# Qwiic_EEPROM.net
KiCad netlist of a schematic drawn in EAGLE
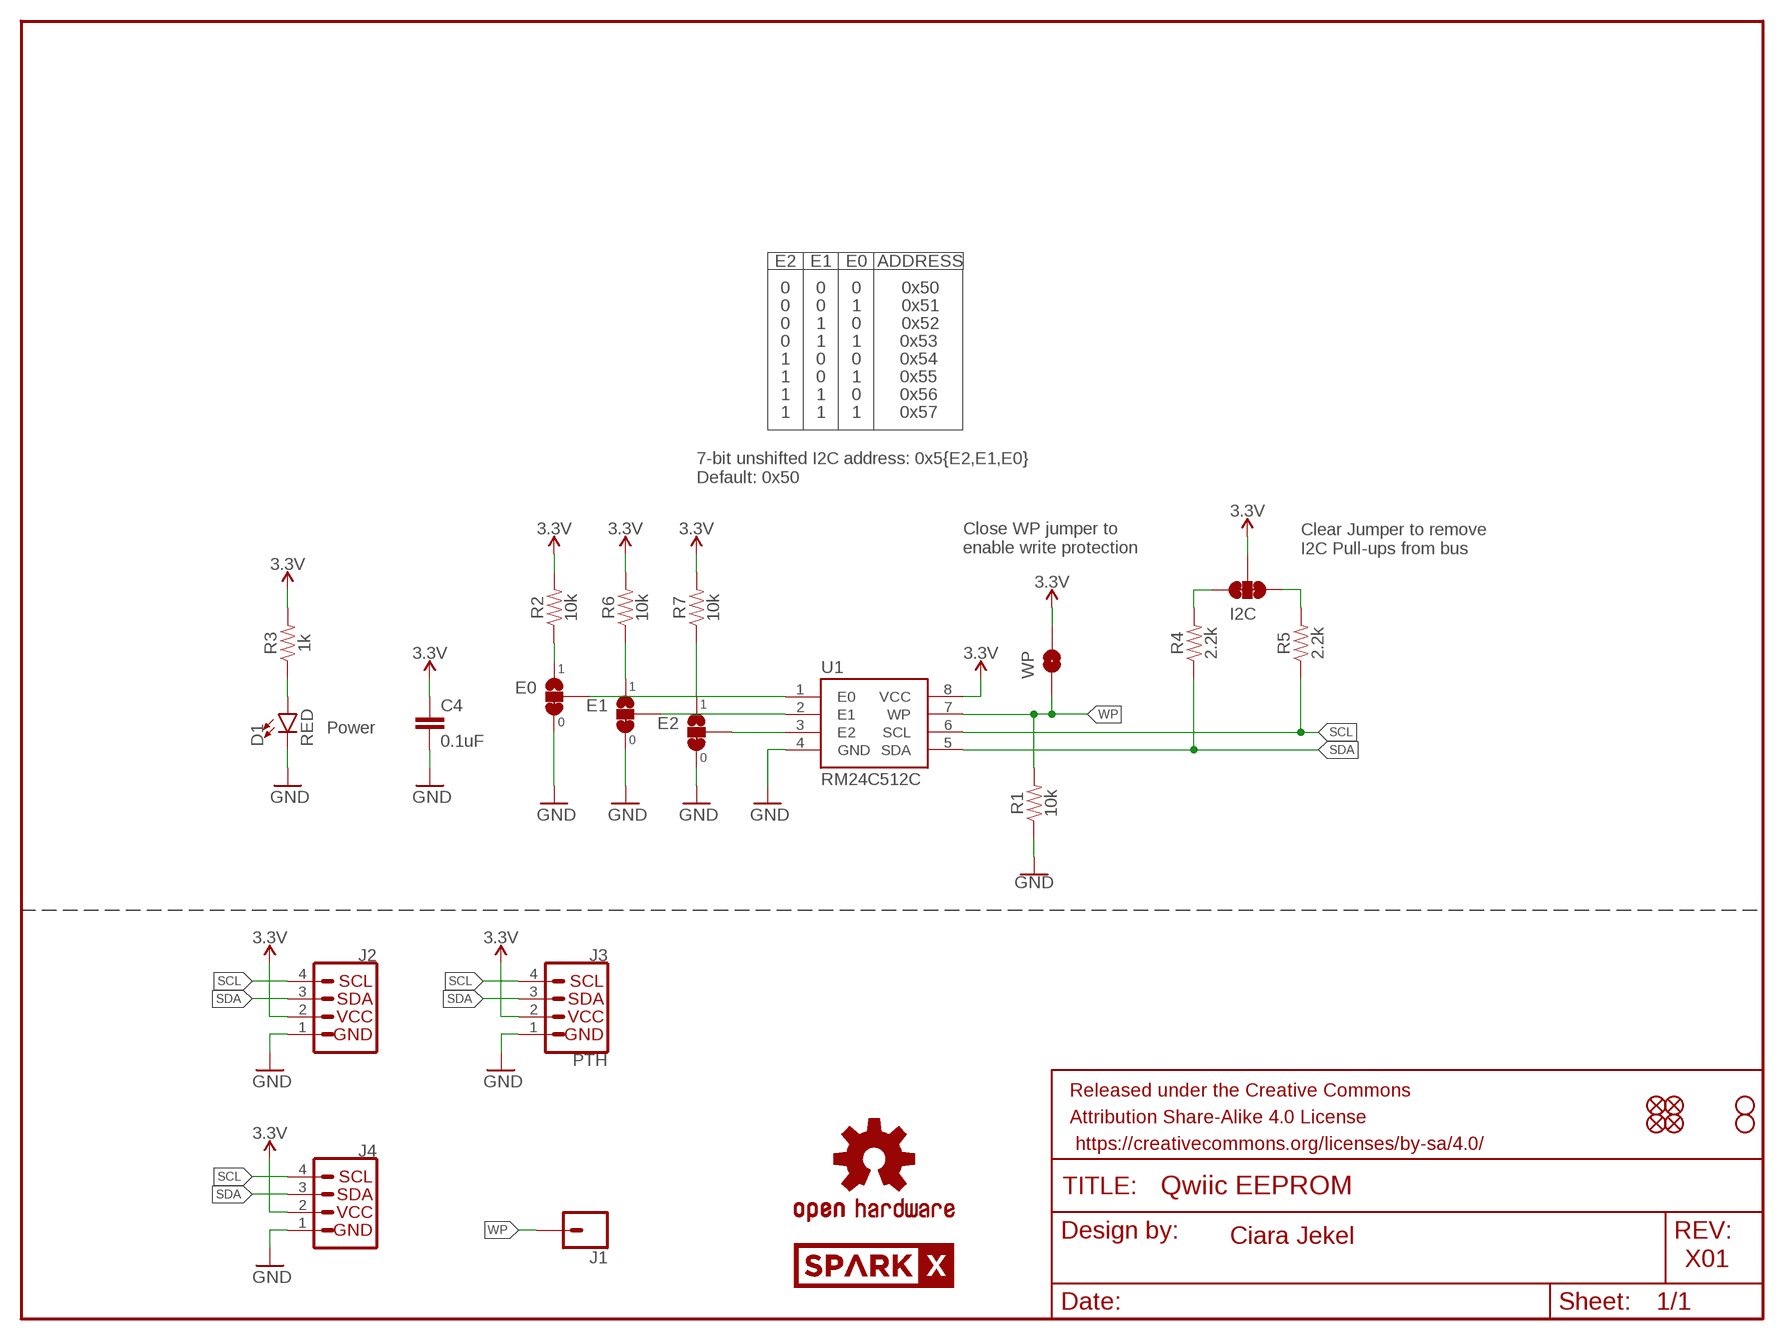
[diagram p0: schematic, sheet 1]

(export (version "E")
  (design (tool "Eeschema 10.0.6"))
  (components
    (comp (ref "C4")
      (value "0.1uF")
      (footprint "eagle-import:0603")
      (libsource (lib "eagle-import") (part "0.1UF-0603-25V-(+80/-20%)"))
    )
    (comp (ref "D1")
      (value "RED")
      (footprint "eagle-import:LED-0603")
      (libsource (lib "eagle-import") (part "LED-RED0603"))
    )
    (comp (ref "E0")
      (value "JUMPER-SMT_3_1-NC_TRACE_SILK")
      (footprint "eagle-import:SMT-JUMPER_3_1-NC_TRACE_SILK")
      (libsource (lib "eagle-import") (part "JUMPER-SMT_3_1-NC_TRACE_SILK"))
    )
    (comp (ref "E1")
      (value "JUMPER-SMT_3_1-NC_TRACE_SILK")
      (footprint "eagle-import:SMT-JUMPER_3_1-NC_TRACE_SILK")
      (libsource (lib "eagle-import") (part "JUMPER-SMT_3_1-NC_TRACE_SILK"))
    )
    (comp (ref "E2")
      (value "JUMPER-SMT_3_1-NC_TRACE_SILK")
      (footprint "eagle-import:SMT-JUMPER_3_1-NC_TRACE_SILK")
      (libsource (lib "eagle-import") (part "JUMPER-SMT_3_1-NC_TRACE_SILK"))
    )
    (comp (ref "FRAME1")
      (value "FRAME-LETTER")
      (footprint "eagle-import:CREATIVE_COMMONS")
      (libsource (lib "eagle-import") (part "FRAME-LETTER"))
    )
    (comp (ref "I2C")
      (value "JUMPER-SMT_3_2-NC_TRACE_SILK")
      (footprint "eagle-import:SMT-JUMPER_3_2-NC_TRACE_SILK")
      (libsource (lib "eagle-import") (part "JUMPER-SMT_3_2-NC_TRACE_SILK"))
    )
    (comp (ref "J1")
      (value "CONN_01PTH_NO_SILK_YES_STOP")
      (footprint "eagle-import:1X01_NO_SILK")
      (libsource (lib "eagle-import") (part "CONN_01PTH_NO_SILK_YES_STOP"))
    )
    (comp (ref "J2")
      (value "QWIIC_CONNECTORJS-1MM")
      (footprint "eagle-import:1X04_1MM_RA")
      (libsource (lib "eagle-import") (part "QWIIC_CONNECTORJS-1MM"))
    )
    (comp (ref "J3")
      (value "PTH")
      (footprint "eagle-import:1X04_NO_SILK")
      (libsource (lib "eagle-import") (part "I2C_STANDARD_NO_SILK"))
    )
    (comp (ref "J4")
      (value "QWIIC_CONNECTORJS-1MM")
      (footprint "eagle-import:1X04_1MM_RA")
      (libsource (lib "eagle-import") (part "QWIIC_CONNECTORJS-1MM"))
    )
    (comp (ref "JP1")
      (value "FIDUCIALUFIDUCIAL")
      (footprint "eagle-import:MICRO-FIDUCIAL")
      (libsource (lib "eagle-import") (part "FIDUCIALUFIDUCIAL"))
    )
    (comp (ref "JP2")
      (value "FIDUCIALUFIDUCIAL")
      (footprint "eagle-import:MICRO-FIDUCIAL")
      (libsource (lib "eagle-import") (part "FIDUCIALUFIDUCIAL"))
    )
    (comp (ref "JP3")
      (value "STAND-OFF")
      (footprint "eagle-import:STAND-OFF")
      (libsource (lib "eagle-import") (part "STAND-OFF"))
    )
    (comp (ref "JP4")
      (value "STAND-OFF")
      (footprint "eagle-import:STAND-OFF")
      (libsource (lib "eagle-import") (part "STAND-OFF"))
    )
    (comp (ref "JP5")
      (value "FIDUCIALUFIDUCIAL")
      (footprint "eagle-import:MICRO-FIDUCIAL")
      (libsource (lib "eagle-import") (part "FIDUCIALUFIDUCIAL"))
    )
    (comp (ref "JP6")
      (value "FIDUCIALUFIDUCIAL")
      (footprint "eagle-import:MICRO-FIDUCIAL")
      (libsource (lib "eagle-import") (part "FIDUCIALUFIDUCIAL"))
    )
    (comp (ref "LOGO1")
      (value "OSHW-LOGOMINI")
      (footprint "eagle-import:OSHW-LOGO-MINI")
      (libsource (lib "eagle-import") (part "OSHW-LOGOMINI"))
    )
    (comp (ref "R1")
      (value "10k")
      (footprint "eagle-import:0603")
      (libsource (lib "eagle-import") (part "10KOHM-0603-1/10W-1%"))
    )
    (comp (ref "R2")
      (value "10k")
      (footprint "eagle-import:0603")
      (libsource (lib "eagle-import") (part "10KOHM-0603-1/10W-1%"))
    )
    (comp (ref "R3")
      (value "1k")
      (footprint "eagle-import:0603")
      (libsource (lib "eagle-import") (part "1KOHM-0603-1/10W-1%"))
    )
    (comp (ref "R4")
      (value "2.2k")
      (footprint "eagle-import:0603")
      (libsource (lib "eagle-import") (part "2.2KOHM-0603-1/10W-1%"))
    )
    (comp (ref "R5")
      (value "2.2k")
      (footprint "eagle-import:0603")
      (libsource (lib "eagle-import") (part "2.2KOHM-0603-1/10W-1%"))
    )
    (comp (ref "R6")
      (value "10k")
      (footprint "eagle-import:0603")
      (libsource (lib "eagle-import") (part "10KOHM-0603-1/10W-1%"))
    )
    (comp (ref "R7")
      (value "10k")
      (footprint "eagle-import:0603")
      (libsource (lib "eagle-import") (part "10KOHM-0603-1/10W-1%"))
    )
    (comp (ref "U$1")
      (value "SPARKX-LOGO4")
      (footprint "eagle-import:SPARKX-MEDIUM")
      (libsource (lib "eagle-import") (part "SPARKX-LOGO4"))
    )
    (comp (ref "U$2")
      (value "SPARKX-LOGO4")
      (footprint "eagle-import:SPARKX-MEDIUM")
      (libsource (lib "eagle-import") (part "SPARKX-LOGO4"))
    )
    (comp (ref "U1")
      (value "RM24C512C")
      (footprint "eagle-import:SO08")
      (libsource (lib "eagle-import") (part "RM24C512C"))
    )
    (comp (ref "WP")
      (value "JUMPER-SMT_2_NO_SILK")
      (footprint "eagle-import:SMT-JUMPER_2_NO_SILK")
      (libsource (lib "eagle-import") (part "JUMPER-SMT_2_NO_SILK"))
    )
  )
  (nets
    (net (code "1") (name "3.3V") (class "Default")
      (node (ref "C4") (pin "1") (pinfunction "1_1") (pintype "passive"))
      (node (ref "I2C") (pin "2") (pinfunction "2_2") (pintype "passive"))
      (node (ref "J2") (pin "2") (pinfunction "2_2") (pintype "power_in"))
      (node (ref "J3") (pin "2") (pinfunction "VCC_2") (pintype "power_in"))
      (node (ref "J4") (pin "2") (pinfunction "2_2") (pintype "power_in"))
      (node (ref "R2") (pin "2") (pinfunction "2_2") (pintype "passive"))
      (node (ref "R3") (pin "2") (pinfunction "2_2") (pintype "passive"))
      (node (ref "R6") (pin "2") (pinfunction "2_2") (pintype "passive"))
      (node (ref "R7") (pin "2") (pinfunction "2_2") (pintype "passive"))
      (node (ref "U1") (pin "8") (pinfunction "VCC_8") (pintype "power_in"))
      (node (ref "WP") (pin "2") (pinfunction "2_2") (pintype "passive"))
    )
    (net (code "2") (name "GND") (class "Default")
      (node (ref "C4") (pin "2") (pinfunction "2_2") (pintype "passive"))
      (node (ref "D1") (pin "C") (pinfunction "C_C") (pintype "passive"))
      (node (ref "E0") (pin "3") (pinfunction "3_3") (pintype "passive"))
      (node (ref "E1") (pin "3") (pinfunction "3_3") (pintype "passive"))
      (node (ref "E2") (pin "3") (pinfunction "3_3") (pintype "passive"))
      (node (ref "J2") (pin "1") (pinfunction "1_1") (pintype "power_in"))
      (node (ref "J3") (pin "1") (pinfunction "GND_1") (pintype "power_in"))
      (node (ref "J4") (pin "1") (pinfunction "1_1") (pintype "power_in"))
      (node (ref "R1") (pin "1") (pinfunction "1_1") (pintype "passive"))
      (node (ref "U1") (pin "4") (pinfunction "GND_4") (pintype "power_in"))
    )
    (net (code "3") (name "Net-(D1-PadA)") (class "Default")
      (node (ref "D1") (pin "A") (pinfunction "A_A") (pintype "passive"))
      (node (ref "R3") (pin "1") (pinfunction "1_1") (pintype "passive"))
    )
    (net (code "4") (name "Net-(E0-Pad1)") (class "Default")
      (node (ref "E0") (pin "1") (pinfunction "1_1") (pintype "passive"))
      (node (ref "R2") (pin "1") (pinfunction "1_1") (pintype "passive"))
    )
    (net (code "5") (name "Net-(E1-Pad1)") (class "Default")
      (node (ref "E1") (pin "1") (pinfunction "1_1") (pintype "passive"))
      (node (ref "R6") (pin "1") (pinfunction "1_1") (pintype "passive"))
    )
    (net (code "6") (name "Net-(E2-Pad1)") (class "Default")
      (node (ref "E2") (pin "1") (pinfunction "1_1") (pintype "passive"))
      (node (ref "R7") (pin "1") (pinfunction "1_1") (pintype "passive"))
    )
    (net (code "7") (name "Net-(I2C-Pad1)") (class "Default")
      (node (ref "I2C") (pin "1") (pinfunction "1_1") (pintype "passive"))
      (node (ref "R5") (pin "2") (pinfunction "2_2") (pintype "passive"))
    )
    (net (code "8") (name "Net-(I2C-Pad3)") (class "Default")
      (node (ref "I2C") (pin "3") (pinfunction "3_3") (pintype "passive"))
      (node (ref "R4") (pin "2") (pinfunction "2_2") (pintype "passive"))
    )
    (net (code "9") (name "Net-(U1-E0)") (class "Default")
      (node (ref "E0") (pin "2") (pinfunction "2_2") (pintype "passive"))
      (node (ref "U1") (pin "1") (pinfunction "E0_1") (pintype "bidirectional"))
    )
    (net (code "10") (name "Net-(U1-E1)") (class "Default")
      (node (ref "E1") (pin "2") (pinfunction "2_2") (pintype "passive"))
      (node (ref "U1") (pin "2") (pinfunction "E1_2") (pintype "bidirectional"))
    )
    (net (code "11") (name "Net-(U1-E2)") (class "Default")
      (node (ref "E2") (pin "2") (pinfunction "2_2") (pintype "passive"))
      (node (ref "U1") (pin "3") (pinfunction "E2_3") (pintype "bidirectional"))
    )
    (net (code "12") (name "SCL") (class "Default")
      (node (ref "J2") (pin "4") (pinfunction "4_4") (pintype "passive"))
      (node (ref "J3") (pin "4") (pinfunction "SCL_4") (pintype "passive"))
      (node (ref "J4") (pin "4") (pinfunction "4_4") (pintype "passive"))
      (node (ref "R5") (pin "1") (pinfunction "1_1") (pintype "passive"))
      (node (ref "U1") (pin "6") (pinfunction "SCL_6") (pintype "bidirectional"))
    )
    (net (code "13") (name "SDA") (class "Default")
      (node (ref "J2") (pin "3") (pinfunction "3_3") (pintype "passive"))
      (node (ref "J3") (pin "3") (pinfunction "SDA_3") (pintype "passive"))
      (node (ref "J4") (pin "3") (pinfunction "3_3") (pintype "passive"))
      (node (ref "R4") (pin "1") (pinfunction "1_1") (pintype "passive"))
      (node (ref "U1") (pin "5") (pinfunction "SDA_5") (pintype "bidirectional"))
    )
    (net (code "14") (name "WP") (class "Default")
      (node (ref "J1") (pin "1") (pinfunction "1_1") (pintype "passive"))
      (node (ref "R1") (pin "2") (pinfunction "2_2") (pintype "passive"))
      (node (ref "U1") (pin "7") (pinfunction "WP_7") (pintype "bidirectional"))
      (node (ref "WP") (pin "1") (pinfunction "1_1") (pintype "passive"))
    )
  )
)
